# Sheet1.net
KiCad netlist of a schematic drawn in Altium Designer
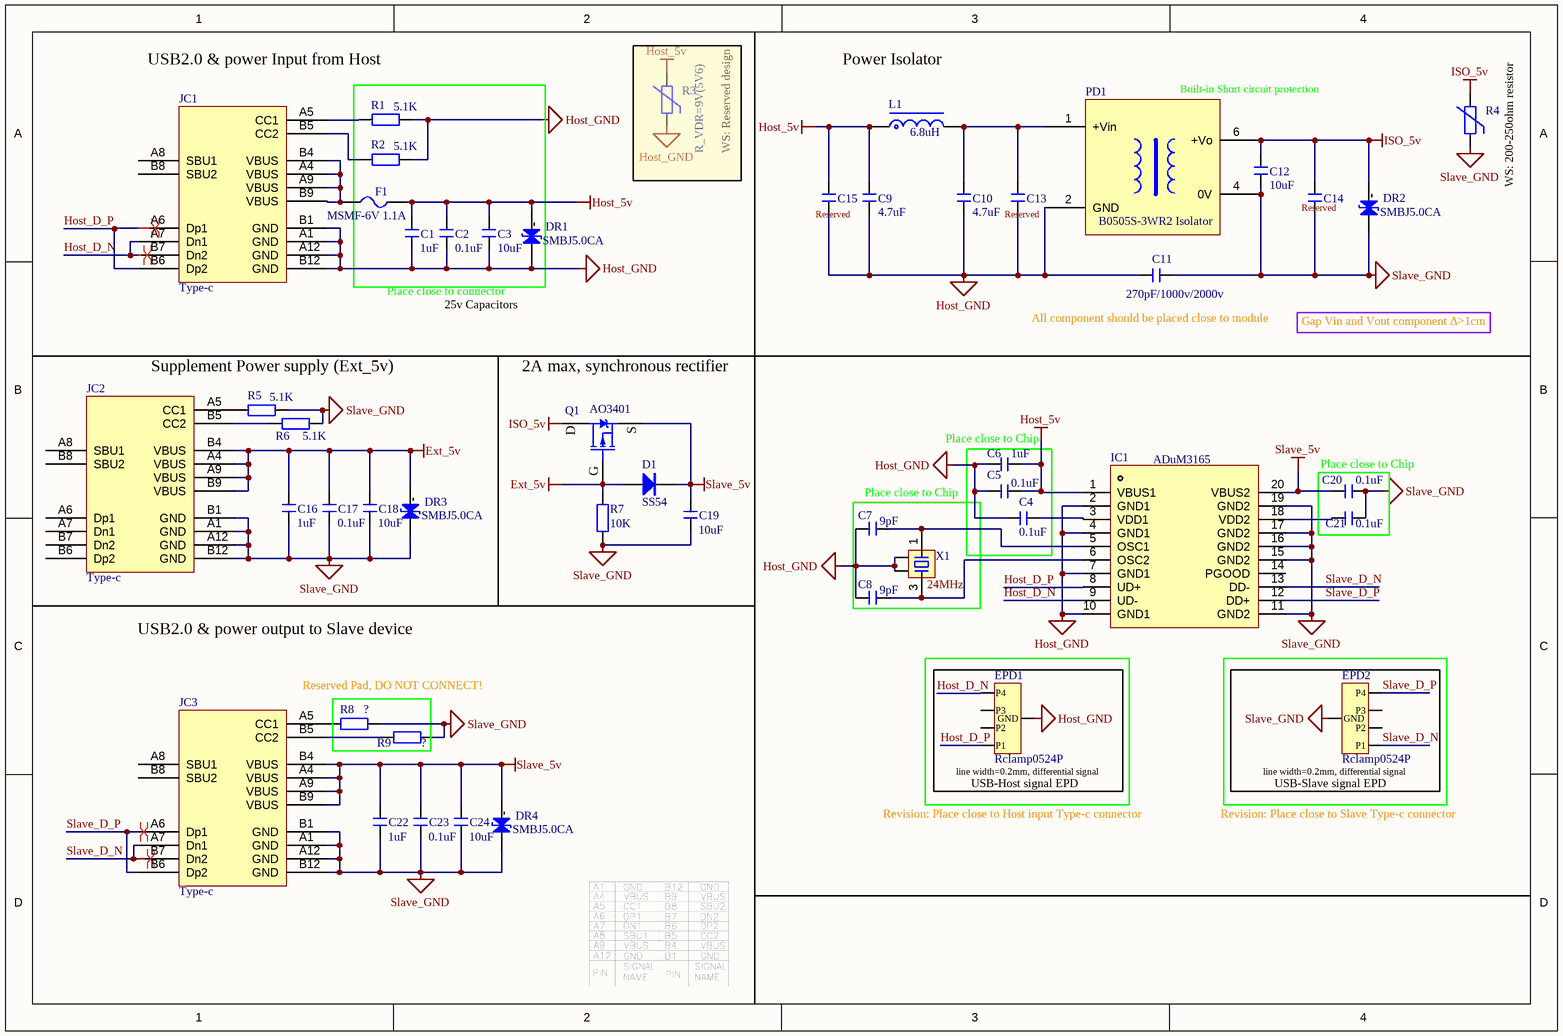
[diagram p0: Sheet1.SchDoc]

(export (version "E")
  (design (tool "Eeschema 10.0.6"))
  (components
    (comp (ref "C1")
      (value "1uF")
      (footprint "0603")
      (description "无极性贴片电容")
      (fields (field (name "版权归属") "源创客"))
      (libsource (lib "Schlib") (part "C"))
    )
    (comp (ref "C2")
      (value "0.1uF")
      (footprint "0603")
      (description "无极性贴片电容")
      (fields (field (name "版权归属") "源创客"))
      (libsource (lib "Schlib") (part "C"))
    )
    (comp (ref "C3")
      (value "10uF")
      (footprint "0603")
      (description "无极性贴片电容")
      (fields (field (name "版权归属") "源创客"))
      (libsource (lib "Schlib") (part "C"))
    )
    (comp (ref "C4")
      (value "0.1uF")
      (footprint "0603")
      (description "无极性贴片电容")
      (fields (field (name "版权归属") "源创客"))
      (libsource (lib "Schlib") (part "C"))
    )
    (comp (ref "C5")
      (value "0.1uF")
      (footprint "0603")
      (description "无极性贴片电容")
      (fields (field (name "版权归属") "源创客"))
      (libsource (lib "Schlib") (part "C"))
    )
    (comp (ref "C6")
      (value "1uF")
      (footprint "0603")
      (description "无极性贴片电容")
      (fields (field (name "版权归属") "源创客"))
      (libsource (lib "Schlib") (part "C"))
    )
    (comp (ref "C7")
      (value "9pF")
      (footprint "0603")
      (description "无极性贴片电容")
      (fields (field (name "版权归属") "源创客"))
      (libsource (lib "Schlib") (part "C"))
    )
    (comp (ref "C8")
      (value "9pF")
      (footprint "0603")
      (description "无极性贴片电容")
      (fields (field (name "版权归属") "源创客"))
      (libsource (lib "Schlib") (part "C"))
    )
    (comp (ref "C9")
      (value "4.7uF")
      (footprint "0603")
      (description "无极性贴片电容")
      (fields (field (name "版权归属") "源创客"))
      (libsource (lib "Schlib") (part "C"))
    )
    (comp (ref "C10")
      (value "4.7uF")
      (footprint "0603")
      (description "无极性贴片电容")
      (fields (field (name "版权归属") "源创客"))
      (libsource (lib "Schlib") (part "C"))
    )
    (comp (ref "C11")
      (value "270pF/1000v/2000v")
      (footprint "1206R")
      (description "无极性贴片电容")
      (fields (field (name "版权归属") "源创客"))
      (libsource (lib "Schlib") (part "C"))
    )
    (comp (ref "C12")
      (value "10uF")
      (footprint "0603")
      (description "无极性贴片电容")
      (fields (field (name "版权归属") "源创客"))
      (libsource (lib "Schlib") (part "C"))
    )
    (comp (ref "C13")
      (value "Reserved")
      (footprint "0603")
      (description "无极性贴片电容")
      (fields (field (name "版权归属") "源创客"))
      (libsource (lib "Schlib") (part "C"))
    )
    (comp (ref "C14")
      (value "Reserved")
      (footprint "0603")
      (description "无极性贴片电容")
      (fields (field (name "版权归属") "源创客"))
      (libsource (lib "Schlib") (part "C"))
    )
    (comp (ref "C15")
      (value "Reserved")
      (footprint "0603")
      (description "无极性贴片电容")
      (fields (field (name "版权归属") "源创客"))
      (libsource (lib "Schlib") (part "C"))
    )
    (comp (ref "C16")
      (value "1uF")
      (footprint "0603")
      (description "无极性贴片电容")
      (fields (field (name "版权归属") "源创客"))
      (libsource (lib "Schlib") (part "C"))
    )
    (comp (ref "C17")
      (value "0.1uF")
      (footprint "0603")
      (description "无极性贴片电容")
      (fields (field (name "版权归属") "源创客"))
      (libsource (lib "Schlib") (part "C"))
    )
    (comp (ref "C18")
      (value "10uF")
      (footprint "0603")
      (description "无极性贴片电容")
      (fields (field (name "版权归属") "源创客"))
      (libsource (lib "Schlib") (part "C"))
    )
    (comp (ref "C19")
      (value "10uF")
      (footprint "0603")
      (description "无极性贴片电容")
      (fields (field (name "版权归属") "源创客"))
      (libsource (lib "Schlib") (part "C"))
    )
    (comp (ref "C20")
      (value "0.1uF")
      (footprint "0603")
      (description "无极性贴片电容")
      (fields (field (name "版权归属") "源创客"))
      (libsource (lib "Schlib") (part "C"))
    )
    (comp (ref "C21")
      (value "0.1uF")
      (footprint "0603")
      (description "无极性贴片电容")
      (fields (field (name "版权归属") "源创客"))
      (libsource (lib "Schlib") (part "C"))
    )
    (comp (ref "C22")
      (value "1uF")
      (footprint "0603")
      (description "无极性贴片电容")
      (fields (field (name "版权归属") "源创客"))
      (libsource (lib "Schlib") (part "C"))
    )
    (comp (ref "C23")
      (value "0.1uF")
      (footprint "0603")
      (description "无极性贴片电容")
      (fields (field (name "版权归属") "源创客"))
      (libsource (lib "Schlib") (part "C"))
    )
    (comp (ref "C24")
      (value "10uF")
      (footprint "0603")
      (description "无极性贴片电容")
      (fields (field (name "版权归属") "源创客"))
      (libsource (lib "Schlib") (part "C"))
    )
    (comp (ref "D1")
      (value "SS54")
      (footprint "SMA/DO-214AC")
      (description "肖特基二极管")
      (fields (field (name "版权归属") "源创客"))
      (libsource (lib "Schlib") (part "SS54"))
    )
    (comp (ref "DR1")
      (value "SMBJ5.0CA")
      (footprint "SMB")
      (description "瞬态电压抑制二极管")
      (fields (field (name "版权归属") "源创客"))
      (libsource (lib "Schlib") (part "SMBJ5.0CA"))
    )
    (comp (ref "DR2")
      (value "SMBJ5.0CA")
      (footprint "SMB")
      (description "瞬态电压抑制二极管")
      (fields (field (name "版权归属") "源创客"))
      (libsource (lib "Schlib") (part "SMBJ5.0CA"))
    )
    (comp (ref "DR3")
      (value "SMBJ5.0CA")
      (footprint "SMB")
      (description "瞬态电压抑制二极管")
      (fields (field (name "版权归属") "源创客"))
      (libsource (lib "Schlib") (part "SMBJ5.0CA"))
    )
    (comp (ref "DR4")
      (value "SMBJ5.0CA")
      (footprint "SMB")
      (description "瞬态电压抑制二极管")
      (fields (field (name "版权归属") "源创客"))
      (libsource (lib "Schlib") (part "SMBJ5.0CA"))
    )
    (comp (ref "EPD1")
      (value "Rclamp0524P")
      (footprint "SLP2510P8")
      (description "Rclamp0524P  Ultra Low Capacitance TVS Arrays")
      (libsource (lib "") (part "Rclamp0524P_1"))
    )
    (comp (ref "EPD2")
      (value "Rclamp0524P")
      (footprint "SLP2510P8")
      (description "Rclamp0524P  Ultra Low Capacitance TVS Arrays")
      (libsource (lib "Schlib") (part "Rclamp0524P"))
    )
    (comp (ref "F1")
      (value "MSMF-6V 1.1A")
      (footprint "FU 1206")
      (description "贴片保险丝")
      (fields (field (name "版权归属") "源创客"))
      (libsource (lib "Schlib") (part "FU"))
    )
    (comp (ref "IC1")
      (value "ADuM3165")
      (footprint "SSOP20")
      (description "3.75kV RMS Digital Isolators for USB2.0 High Speed")
      (libsource (lib "Schlib") (part "ADuM3165"))
    )
    (comp (ref "JC1")
      (value "Type-c")
      (footprint "TYPE-C-SMD_TYPE-C-31-M-41")
      (libsource (lib "Schlib") (part "Type-C"))
    )
    (comp (ref "JC2")
      (value "Type-c")
      (footprint "TYPE-C-SMD_TYPE-C-31-M-41")
      (libsource (lib "Schlib") (part "Type-C"))
    )
    (comp (ref "JC3")
      (value "Type-c")
      (footprint "TYPE-C-SMD_TYPE-C-31-M-41")
      (libsource (lib "Schlib") (part "Type-C"))
    )
    (comp (ref "L1")
      (value "6.8uH")
      (footprint "CD43")
      (description "贴片功率电感")
      (fields (field (name "版权归属") "源创客"))
      (libsource (lib "Schlib") (part "L-CD"))
    )
    (comp (ref "PD1")
      (value "B0505S-3WR2 Isolator")
      (footprint "B0505S-3WR2 K-CUT")
      (description "K-CUT 05v - 05v power isolator")
      (libsource (lib "Schlib") (part "B0505S-3WR2"))
    )
    (comp (ref "Q1")
      (value "AO3401")
      (footprint "SOT23")
      (description "P沟增强型场效应管")
      (fields (field (name "版权归属") "源创客"))
      (libsource (lib "Schlib") (part "AO3401"))
    )
    (comp (ref "R1")
      (value "5.1K")
      (footprint "0603")
      (description "贴片电阻")
      (fields (field (name "版权归属") "源创客"))
      (libsource (lib "Schlib") (part "R"))
    )
    (comp (ref "R2")
      (value "5.1K")
      (footprint "0603")
      (description "贴片电阻")
      (fields (field (name "版权归属") "源创客"))
      (libsource (lib "Schlib") (part "R"))
    )
    (comp (ref "R3")
      (value "R_VDR=9V(5V6)")
      (footprint "1206R")
      (description "压敏电阻")
      (fields (field (name "版权归属") "源创客"))
      (libsource (lib "Schlib") (part "R_VDR"))
    )
    (comp (ref "R4")
      (value "~")
      (footprint "1206R")
      (description "压敏电阻")
      (fields (field (name "版权归属") "源创客"))
      (libsource (lib "Schlib") (part "R_VDR"))
    )
    (comp (ref "R5")
      (value "5.1K")
      (footprint "0603")
      (description "贴片电阻")
      (fields (field (name "版权归属") "源创客"))
      (libsource (lib "Schlib") (part "R"))
    )
    (comp (ref "R6")
      (value "5.1K")
      (footprint "0603")
      (description "贴片电阻")
      (fields (field (name "版权归属") "源创客"))
      (libsource (lib "Schlib") (part "R"))
    )
    (comp (ref "R7")
      (value "10K")
      (footprint "0603")
      (description "贴片电阻")
      (fields (field (name "版权归属") "源创客"))
      (libsource (lib "Schlib") (part "R"))
    )
    (comp (ref "R8")
      (value "?")
      (footprint "0603")
      (description "贴片电阻")
      (fields (field (name "版权归属") "源创客"))
      (libsource (lib "Schlib") (part "R"))
    )
    (comp (ref "R9")
      (value "?")
      (footprint "0603")
      (description "贴片电阻")
      (fields (field (name "版权归属") "源创客"))
      (libsource (lib "Schlib") (part "R"))
    )
    (comp (ref "X1")
      (value "24MHz")
      (footprint "OSC 3225-4P")
      (description "4脚无源晶振")
      (fields (field (name "版权归属") "源创客"))
      (libsource (lib "Schlib") (part "XTAL-4P"))
    )
  )
  (nets
    (net (code "1") (name "/Host_D_N") (class "Default")
      (node (ref "EPD1") (pin "5") (pinfunction "P4_5") (pintype "passive"))
      (node (ref "IC1") (pin "9") (pinfunction "UD-_9") (pintype "passive"))
      (node (ref "JC1") (pin "A7") (pinfunction "Dn1_A7") (pintype "passive"))
      (node (ref "JC1") (pin "B7") (pinfunction "Dn2_B7") (pintype "passive"))
    )
    (net (code "2") (name "/Host_D_P") (class "Default")
      (node (ref "EPD1") (pin "1") (pinfunction "P1_1") (pintype "passive"))
      (node (ref "IC1") (pin "8") (pinfunction "UD+_8") (pintype "passive"))
      (node (ref "JC1") (pin "A6") (pinfunction "Dp1_A6") (pintype "passive"))
      (node (ref "JC1") (pin "B6") (pinfunction "Dp2_B6") (pintype "passive"))
    )
    (net (code "3") (name "/Slave_D_N") (class "Default")
      (node (ref "EPD2") (pin "1") (pinfunction "P1_1") (pintype "passive"))
      (node (ref "IC1") (pin "13") (pinfunction "DD-_13") (pintype "passive"))
      (node (ref "JC3") (pin "A7") (pinfunction "Dn1_A7") (pintype "passive"))
      (node (ref "JC3") (pin "B7") (pinfunction "Dn2_B7") (pintype "passive"))
    )
    (net (code "4") (name "/Slave_D_P") (class "Default")
      (node (ref "EPD2") (pin "5") (pinfunction "P4_5") (pintype "passive"))
      (node (ref "IC1") (pin "12") (pinfunction "DD+_12") (pintype "passive"))
      (node (ref "JC3") (pin "A6") (pinfunction "Dp1_A6") (pintype "passive"))
      (node (ref "JC3") (pin "B6") (pinfunction "Dp2_B6") (pintype "passive"))
    )
    (net (code "5") (name "Ext_5v") (class "Default")
      (node (ref "C16") (pin "1") (pinfunction "1_1") (pintype "passive"))
      (node (ref "C17") (pin "1") (pinfunction "1_1") (pintype "passive"))
      (node (ref "C18") (pin "1") (pinfunction "1_1") (pintype "passive"))
      (node (ref "D1") (pin "1") (pinfunction "A_1") (pintype "passive"))
      (node (ref "DR3") (pin "2") (pinfunction "K_2") (pintype "passive"))
      (node (ref "JC2") (pin "A4") (pinfunction "VBUS_A4") (pintype "passive"))
      (node (ref "JC2") (pin "A9") (pinfunction "VBUS_A9") (pintype "passive"))
      (node (ref "JC2") (pin "B4") (pinfunction "VBUS_B4") (pintype "passive"))
      (node (ref "JC2") (pin "B9") (pinfunction "VBUS_B9") (pintype "passive"))
      (node (ref "Q1") (pin "1") (pinfunction "G_1") (pintype "passive"))
      (node (ref "R7") (pin "1") (pinfunction "1_1") (pintype "passive"))
    )
    (net (code "6") (name "Host_5v") (class "Default")
      (node (ref "C1") (pin "1") (pinfunction "1_1") (pintype "passive"))
      (node (ref "C15") (pin "1") (pinfunction "1_1") (pintype "passive"))
      (node (ref "C2") (pin "1") (pinfunction "1_1") (pintype "passive"))
      (node (ref "C3") (pin "1") (pinfunction "1_1") (pintype "passive"))
      (node (ref "C5") (pin "2") (pinfunction "2_2") (pintype "passive"))
      (node (ref "C6") (pin "2") (pinfunction "2_2") (pintype "passive"))
      (node (ref "C9") (pin "1") (pinfunction "1_1") (pintype "passive"))
      (node (ref "DR1") (pin "2") (pinfunction "K_2") (pintype "passive"))
      (node (ref "F1") (pin "2") (pinfunction "2_2") (pintype "passive"))
      (node (ref "IC1") (pin "1") (pinfunction "VBUS1_1") (pintype "passive"))
      (node (ref "L1") (pin "1") (pinfunction "1_1") (pintype "passive"))
      (node (ref "R3") (pin "2") (pinfunction "2_2") (pintype "passive"))
    )
    (net (code "7") (name "Host_GND") (class "Default")
      (node (ref "C1") (pin "2") (pinfunction "2_2") (pintype "passive"))
      (node (ref "C10") (pin "2") (pinfunction "2_2") (pintype "passive"))
      (node (ref "C11") (pin "1") (pinfunction "1_1") (pintype "passive"))
      (node (ref "C13") (pin "2") (pinfunction "2_2") (pintype "passive"))
      (node (ref "C15") (pin "2") (pinfunction "2_2") (pintype "passive"))
      (node (ref "C2") (pin "2") (pinfunction "2_2") (pintype "passive"))
      (node (ref "C3") (pin "2") (pinfunction "2_2") (pintype "passive"))
      (node (ref "C4") (pin "2") (pinfunction "2_2") (pintype "passive"))
      (node (ref "C5") (pin "1") (pinfunction "1_1") (pintype "passive"))
      (node (ref "C6") (pin "1") (pinfunction "1_1") (pintype "passive"))
      (node (ref "C7") (pin "1") (pinfunction "1_1") (pintype "passive"))
      (node (ref "C8") (pin "1") (pinfunction "1_1") (pintype "passive"))
      (node (ref "C9") (pin "2") (pinfunction "2_2") (pintype "passive"))
      (node (ref "DR1") (pin "1") (pinfunction "A_1") (pintype "passive"))
      (node (ref "EPD1") (pin "3") (pinfunction "GND_3") (pintype "passive"))
      (node (ref "IC1") (pin "10") (pinfunction "GND1_10") (pintype "passive"))
      (node (ref "IC1") (pin "2") (pinfunction "GND1_2") (pintype "passive"))
      (node (ref "IC1") (pin "4") (pinfunction "GND1_4") (pintype "passive"))
      (node (ref "IC1") (pin "7") (pinfunction "GND1_7") (pintype "passive"))
      (node (ref "JC1") (pin "A1") (pinfunction "GND_A1") (pintype "passive"))
      (node (ref "JC1") (pin "A12") (pinfunction "GND_A12") (pintype "passive"))
      (node (ref "JC1") (pin "B1") (pinfunction "GND_B1") (pintype "passive"))
      (node (ref "JC1") (pin "B12") (pinfunction "GND_B12") (pintype "passive"))
      (node (ref "PD1") (pin "2") (pinfunction "GND_2") (pintype "passive"))
      (node (ref "R1") (pin "2") (pinfunction "2_2") (pintype "passive"))
      (node (ref "R2") (pin "2") (pinfunction "2_2") (pintype "passive"))
      (node (ref "R3") (pin "1") (pinfunction "1_1") (pintype "passive"))
      (node (ref "X1") (pin "2") (pinfunction "2_2") (pintype "passive"))
      (node (ref "X1") (pin "4") (pinfunction "4_4") (pintype "passive"))
    )
    (net (code "8") (name "ISO_5v") (class "Default")
      (node (ref "C12") (pin "1") (pinfunction "1_1") (pintype "passive"))
      (node (ref "C14") (pin "1") (pinfunction "1_1") (pintype "passive"))
      (node (ref "DR2") (pin "2") (pinfunction "K_2") (pintype "passive"))
      (node (ref "PD1") (pin "6") (pinfunction "+Vo_6") (pintype "passive"))
      (node (ref "Q1") (pin "2") (pinfunction "D_2") (pintype "passive"))
      (node (ref "R4") (pin "2") (pinfunction "2_2") (pintype "passive"))
    )
    (net (code "9") (name "Net-(F1-Pad1)") (class "Default")
      (node (ref "F1") (pin "1") (pinfunction "1_1") (pintype "passive"))
      (node (ref "JC1") (pin "A4") (pinfunction "VBUS_A4") (pintype "passive"))
      (node (ref "JC1") (pin "A9") (pinfunction "VBUS_A9") (pintype "passive"))
      (node (ref "JC1") (pin "B4") (pinfunction "VBUS_B4") (pintype "passive"))
      (node (ref "JC1") (pin "B9") (pinfunction "VBUS_B9") (pintype "passive"))
    )
    (net (code "10") (name "Net-(IC1-OSC1)") (class "Default")
      (node (ref "C7") (pin "2") (pinfunction "2_2") (pintype "passive"))
      (node (ref "IC1") (pin "5") (pinfunction "OSC1_5") (pintype "passive"))
      (node (ref "X1") (pin "1") (pinfunction "1_1") (pintype "passive"))
    )
    (net (code "11") (name "Net-(IC1-OSC2)") (class "Default")
      (node (ref "C8") (pin "2") (pinfunction "2_2") (pintype "passive"))
      (node (ref "IC1") (pin "6") (pinfunction "OSC2_6") (pintype "passive"))
      (node (ref "X1") (pin "3") (pinfunction "3_3") (pintype "passive"))
    )
    (net (code "12") (name "Net-(IC1-VDD1)") (class "Default")
      (node (ref "C4") (pin "1") (pinfunction "1_1") (pintype "passive"))
      (node (ref "IC1") (pin "3") (pinfunction "VDD1_3") (pintype "passive"))
    )
    (net (code "13") (name "Net-(IC1-VDD2)") (class "Default")
      (node (ref "C21") (pin "1") (pinfunction "1_1") (pintype "passive"))
      (node (ref "IC1") (pin "18") (pinfunction "VDD2_18") (pintype "passive"))
    )
    (net (code "14") (name "Net-(JC1-CC1)") (class "Default")
      (node (ref "JC1") (pin "A5") (pinfunction "CC1_A5") (pintype "passive"))
      (node (ref "R1") (pin "1") (pinfunction "1_1") (pintype "passive"))
    )
    (net (code "15") (name "Net-(JC1-CC2)") (class "Default")
      (node (ref "JC1") (pin "B5") (pinfunction "CC2_B5") (pintype "passive"))
      (node (ref "R2") (pin "1") (pinfunction "1_1") (pintype "passive"))
    )
    (net (code "16") (name "Net-(JC2-CC1)") (class "Default")
      (node (ref "JC2") (pin "A5") (pinfunction "CC1_A5") (pintype "passive"))
      (node (ref "R5") (pin "1") (pinfunction "1_1") (pintype "passive"))
    )
    (net (code "17") (name "Net-(JC2-CC2)") (class "Default")
      (node (ref "JC2") (pin "B5") (pinfunction "CC2_B5") (pintype "passive"))
      (node (ref "R6") (pin "1") (pinfunction "1_1") (pintype "passive"))
    )
    (net (code "18") (name "Net-(JC3-CC1)") (class "Default")
      (node (ref "JC3") (pin "A5") (pinfunction "CC1_A5") (pintype "passive"))
      (node (ref "R8") (pin "1") (pinfunction "1_1") (pintype "passive"))
    )
    (net (code "19") (name "Net-(JC3-CC2)") (class "Default")
      (node (ref "JC3") (pin "B5") (pinfunction "CC2_B5") (pintype "passive"))
      (node (ref "R9") (pin "1") (pinfunction "1_1") (pintype "passive"))
    )
    (net (code "20") (name "Net-(PD1-+Vin)") (class "Default")
      (node (ref "C10") (pin "1") (pinfunction "1_1") (pintype "passive"))
      (node (ref "C13") (pin "1") (pinfunction "1_1") (pintype "passive"))
      (node (ref "L1") (pin "2") (pinfunction "2_2") (pintype "passive"))
      (node (ref "PD1") (pin "1") (pinfunction "+Vin_1") (pintype "passive"))
    )
    (net (code "21") (name "Slave_5v") (class "Default")
      (node (ref "C19") (pin "1") (pinfunction "1_1") (pintype "passive"))
      (node (ref "C20") (pin "2") (pinfunction "2_2") (pintype "passive"))
      (node (ref "C22") (pin "1") (pinfunction "1_1") (pintype "passive"))
      (node (ref "C23") (pin "1") (pinfunction "1_1") (pintype "passive"))
      (node (ref "C24") (pin "1") (pinfunction "1_1") (pintype "passive"))
      (node (ref "D1") (pin "2") (pinfunction "K_2") (pintype "passive"))
      (node (ref "DR4") (pin "2") (pinfunction "K_2") (pintype "passive"))
      (node (ref "IC1") (pin "20") (pinfunction "VBUS2_20") (pintype "passive"))
      (node (ref "JC3") (pin "A4") (pinfunction "VBUS_A4") (pintype "passive"))
      (node (ref "JC3") (pin "A9") (pinfunction "VBUS_A9") (pintype "passive"))
      (node (ref "JC3") (pin "B4") (pinfunction "VBUS_B4") (pintype "passive"))
      (node (ref "JC3") (pin "B9") (pinfunction "VBUS_B9") (pintype "passive"))
      (node (ref "Q1") (pin "3") (pinfunction "S_3") (pintype "passive"))
    )
    (net (code "22") (name "Slave_GND") (class "Default")
      (node (ref "C11") (pin "2") (pinfunction "2_2") (pintype "passive"))
      (node (ref "C12") (pin "2") (pinfunction "2_2") (pintype "passive"))
      (node (ref "C14") (pin "2") (pinfunction "2_2") (pintype "passive"))
      (node (ref "C16") (pin "2") (pinfunction "2_2") (pintype "passive"))
      (node (ref "C17") (pin "2") (pinfunction "2_2") (pintype "passive"))
      (node (ref "C18") (pin "2") (pinfunction "2_2") (pintype "passive"))
      (node (ref "C19") (pin "2") (pinfunction "2_2") (pintype "passive"))
      (node (ref "C20") (pin "1") (pinfunction "1_1") (pintype "passive"))
      (node (ref "C21") (pin "2") (pinfunction "2_2") (pintype "passive"))
      (node (ref "C22") (pin "2") (pinfunction "2_2") (pintype "passive"))
      (node (ref "C23") (pin "2") (pinfunction "2_2") (pintype "passive"))
      (node (ref "C24") (pin "2") (pinfunction "2_2") (pintype "passive"))
      (node (ref "DR2") (pin "1") (pinfunction "A_1") (pintype "passive"))
      (node (ref "DR3") (pin "1") (pinfunction "A_1") (pintype "passive"))
      (node (ref "DR4") (pin "1") (pinfunction "A_1") (pintype "passive"))
      (node (ref "EPD2") (pin "3") (pinfunction "GND_3") (pintype "passive"))
      (node (ref "IC1") (pin "11") (pinfunction "GND2_11") (pintype "passive"))
      (node (ref "IC1") (pin "15") (pinfunction "GND2_15") (pintype "passive"))
      (node (ref "IC1") (pin "16") (pinfunction "GND2_16") (pintype "passive"))
      (node (ref "IC1") (pin "17") (pinfunction "GND2_17") (pintype "passive"))
      (node (ref "IC1") (pin "19") (pinfunction "GND2_19") (pintype "passive"))
      (node (ref "JC2") (pin "A1") (pinfunction "GND_A1") (pintype "passive"))
      (node (ref "JC2") (pin "A12") (pinfunction "GND_A12") (pintype "passive"))
      (node (ref "JC2") (pin "B1") (pinfunction "GND_B1") (pintype "passive"))
      (node (ref "JC2") (pin "B12") (pinfunction "GND_B12") (pintype "passive"))
      (node (ref "JC3") (pin "A1") (pinfunction "GND_A1") (pintype "passive"))
      (node (ref "JC3") (pin "A12") (pinfunction "GND_A12") (pintype "passive"))
      (node (ref "JC3") (pin "B1") (pinfunction "GND_B1") (pintype "passive"))
      (node (ref "JC3") (pin "B12") (pinfunction "GND_B12") (pintype "passive"))
      (node (ref "PD1") (pin "4") (pinfunction "0V_4") (pintype "passive"))
      (node (ref "R4") (pin "1") (pinfunction "1_1") (pintype "passive"))
      (node (ref "R5") (pin "2") (pinfunction "2_2") (pintype "passive"))
      (node (ref "R6") (pin "2") (pinfunction "2_2") (pintype "passive"))
      (node (ref "R7") (pin "2") (pinfunction "2_2") (pintype "passive"))
      (node (ref "R8") (pin "2") (pinfunction "2_2") (pintype "passive"))
      (node (ref "R9") (pin "2") (pinfunction "2_2") (pintype "passive"))
    )
    (net (code "23") (name "unconnected-(EPD1-P2-Pad2)") (class "Default")
      (node (ref "EPD1") (pin "2") (pinfunction "P2_2") (pintype "passive"))
    )
    (net (code "24") (name "unconnected-(EPD1-P3-Pad4)") (class "Default")
      (node (ref "EPD1") (pin "4") (pinfunction "P3_4") (pintype "passive"))
    )
    (net (code "25") (name "unconnected-(EPD2-P2-Pad2)") (class "Default")
      (node (ref "EPD2") (pin "2") (pinfunction "P2_2") (pintype "passive"))
    )
    (net (code "26") (name "unconnected-(EPD2-P3-Pad4)") (class "Default")
      (node (ref "EPD2") (pin "4") (pinfunction "P3_4") (pintype "passive"))
    )
    (net (code "27") (name "unconnected-(IC1-PGOOD-Pad14)") (class "Default")
      (node (ref "IC1") (pin "14") (pinfunction "PGOOD_14") (pintype "passive"))
    )
    (net (code "28") (name "unconnected-(JC1-SBU1-PadA8)") (class "Default")
      (node (ref "JC1") (pin "A8") (pinfunction "SBU1_A8") (pintype "passive"))
    )
    (net (code "29") (name "unconnected-(JC1-SBU2-PadB8)") (class "Default")
      (node (ref "JC1") (pin "B8") (pinfunction "SBU2_B8") (pintype "passive"))
    )
    (net (code "30") (name "unconnected-(JC2-Dn1-PadA7)") (class "Default")
      (node (ref "JC2") (pin "A7") (pinfunction "Dn1_A7") (pintype "passive"))
    )
    (net (code "31") (name "unconnected-(JC2-Dn2-PadB7)") (class "Default")
      (node (ref "JC2") (pin "B7") (pinfunction "Dn2_B7") (pintype "passive"))
    )
    (net (code "32") (name "unconnected-(JC2-Dp1-PadA6)") (class "Default")
      (node (ref "JC2") (pin "A6") (pinfunction "Dp1_A6") (pintype "passive"))
    )
    (net (code "33") (name "unconnected-(JC2-Dp2-PadB6)") (class "Default")
      (node (ref "JC2") (pin "B6") (pinfunction "Dp2_B6") (pintype "passive"))
    )
    (net (code "34") (name "unconnected-(JC2-SBU1-PadA8)") (class "Default")
      (node (ref "JC2") (pin "A8") (pinfunction "SBU1_A8") (pintype "passive"))
    )
    (net (code "35") (name "unconnected-(JC2-SBU2-PadB8)") (class "Default")
      (node (ref "JC2") (pin "B8") (pinfunction "SBU2_B8") (pintype "passive"))
    )
    (net (code "36") (name "unconnected-(JC3-SBU1-PadA8)") (class "Default")
      (node (ref "JC3") (pin "A8") (pinfunction "SBU1_A8") (pintype "passive"))
    )
    (net (code "37") (name "unconnected-(JC3-SBU2-PadB8)") (class "Default")
      (node (ref "JC3") (pin "B8") (pinfunction "SBU2_B8") (pintype "passive"))
    )
  )
)
